# sandwich-logger.net
KiCad netlist of a schematic drawn in EAGLE
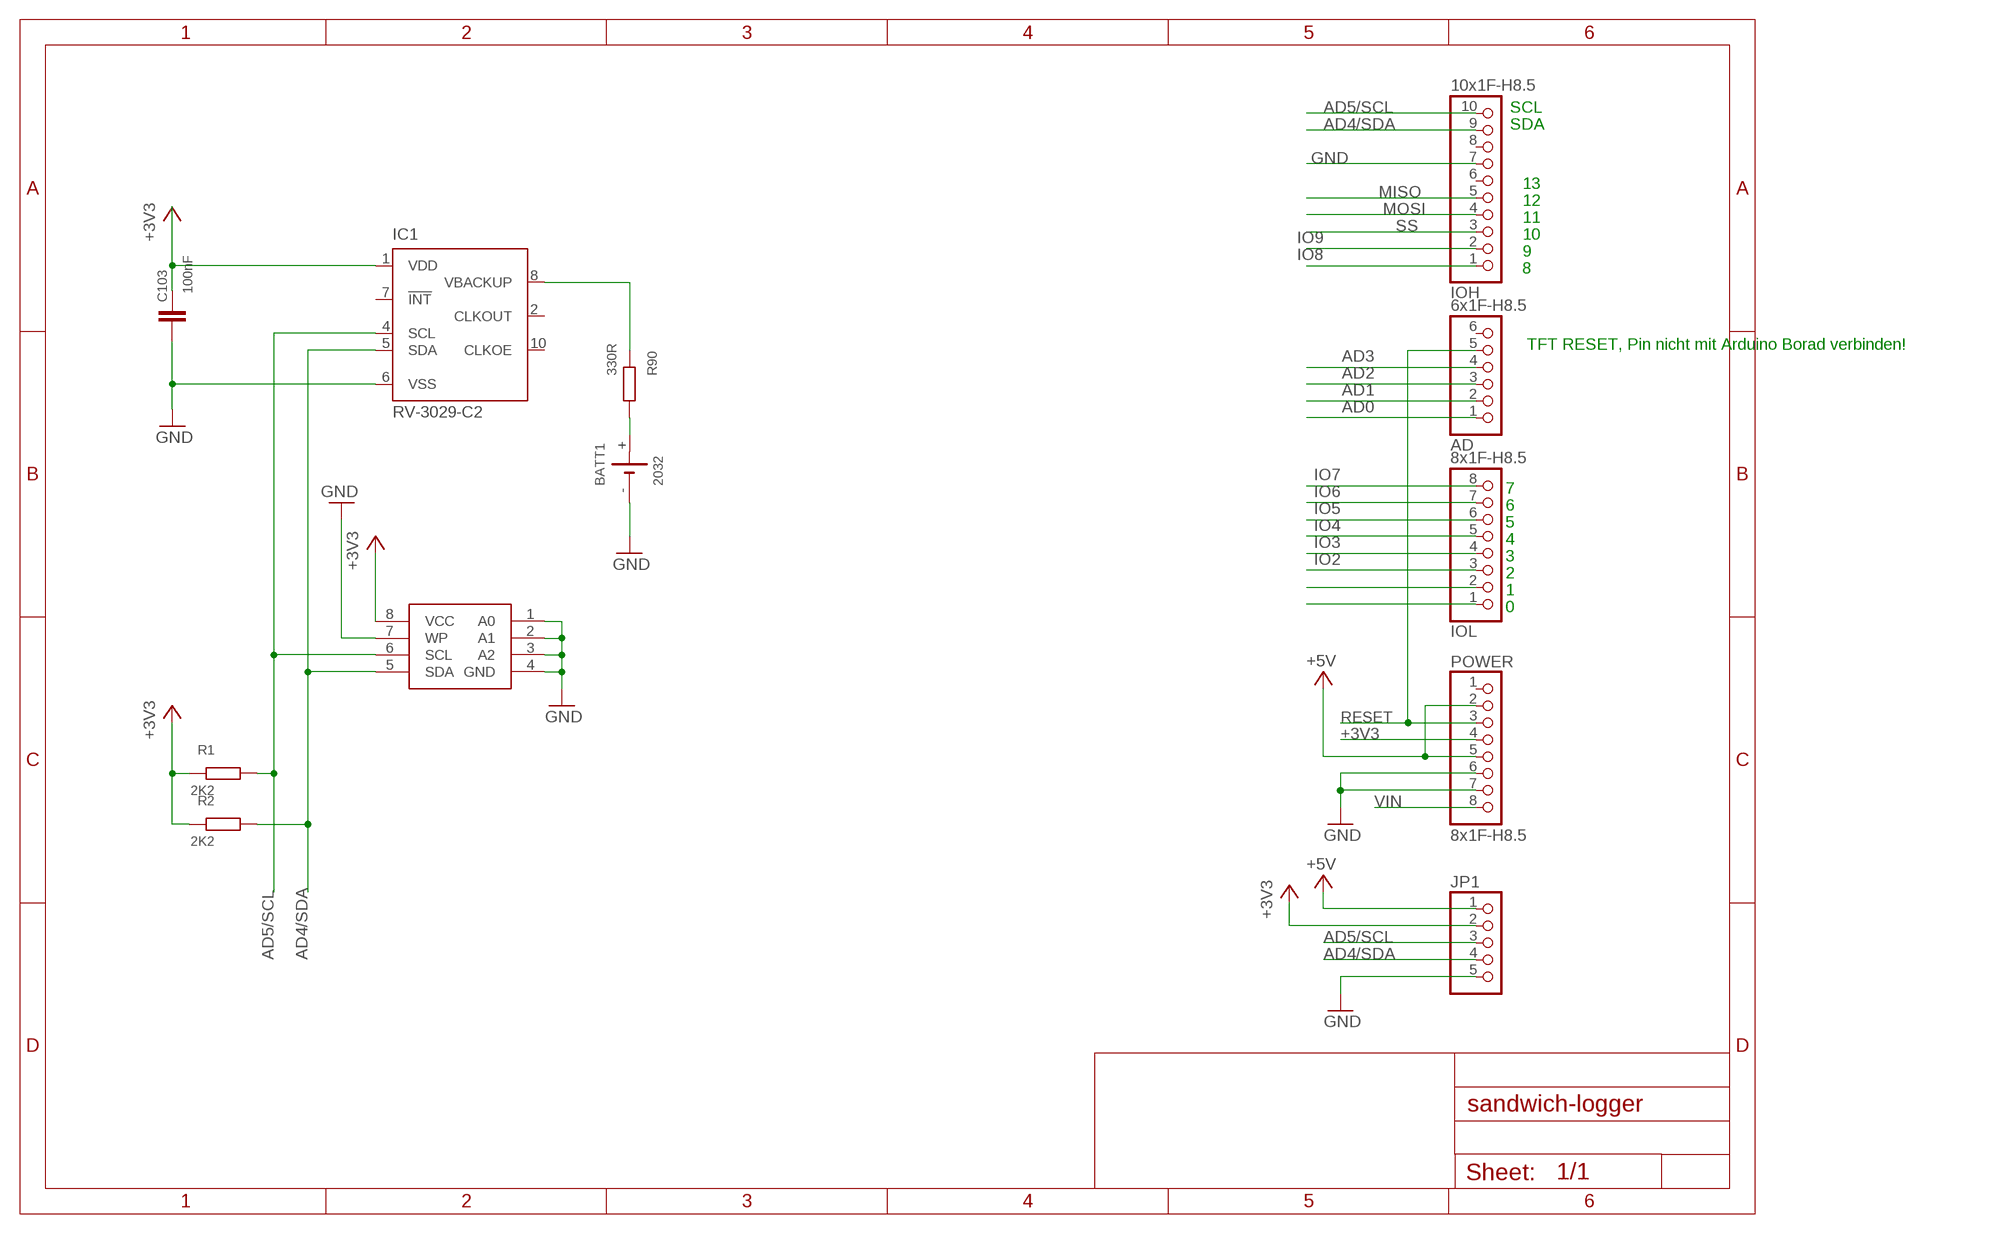
[diagram p0: schematic, sheet 1]

(export (version "E")
  (design (tool "Eeschema 10.0.6"))
  (components
    (comp (ref "AD")
      (value "6x1F-H8.5")
      (footprint "eagle-import:1X06")
      (libsource (lib "eagle-import") (part "PINHD-1X6"))
    )
    (comp (ref "BATT1")
      (value "2032")
      (footprint "eagle-import:2032_SMD")
      (libsource (lib "eagle-import") (part "CR2032_HOLDSMD"))
    )
    (comp (ref "C103")
      (value "100nF")
      (footprint "eagle-import:C0603")
      (libsource (lib "eagle-import") (part "C-EUC0603"))
    )
    (comp (ref "IC1")
      (value "RV-3029-C2")
      (footprint "eagle-import:SON-10")
      (libsource (lib "eagle-import") (part "RV-3029-C2"))
    )
    (comp (ref "IC3")
      (value "AT24C32")
      (footprint "eagle-import:SOIC08")
      (libsource (lib "eagle-import") (part "24C32"))
    )
    (comp (ref "IOH")
      (value "10x1F-H8.5")
      (footprint "eagle-import:1X10")
      (libsource (lib "eagle-import") (part "PINHD-1X10_ARD"))
    )
    (comp (ref "IOL")
      (value "8x1F-H8.5")
      (footprint "eagle-import:1X08")
      (libsource (lib "eagle-import") (part "PINHD-1X8"))
    )
    (comp (ref "JP1")
      (value "PINHD-1X5/90")
      (footprint "eagle-import:1X05_90")
      (libsource (lib "eagle-import") (part "PINHD-1X5/90"))
    )
    (comp (ref "POWER")
      (value "8x1F-H8.5")
      (footprint "eagle-import:1X08")
      (libsource (lib "eagle-import") (part "PINHD-1X8"))
    )
    (comp (ref "R1")
      (value "2K2")
      (footprint "eagle-import:R0603")
      (libsource (lib "eagle-import") (part "R-EU_R0603"))
    )
    (comp (ref "R2")
      (value "2K2")
      (footprint "eagle-import:R0603")
      (libsource (lib "eagle-import") (part "R-EU_R0603"))
    )
    (comp (ref "R90")
      (value "330R")
      (footprint "eagle-import:R0603")
      (libsource (lib "eagle-import") (part "R-EU_R0603"))
    )
  )
  (nets
    (net (code "1") (name "+3V3") (class "Default")
      (node (ref "C103") (pin "1") (pinfunction "1_1") (pintype "passive"))
      (node (ref "IC1") (pin "1") (pinfunction "VDD_1") (pintype "power_in"))
      (node (ref "IC3") (pin "8") (pinfunction "VCC_8") (pintype "bidirectional"))
      (node (ref "JP1") (pin "2") (pinfunction "2_2") (pintype "passive"))
      (node (ref "POWER") (pin "4") (pinfunction "4_4") (pintype "passive"))
      (node (ref "R1") (pin "2") (pinfunction "2_2") (pintype "passive"))
      (node (ref "R2") (pin "2") (pinfunction "2_2") (pintype "passive"))
    )
    (net (code "2") (name "+5V") (class "Default")
      (node (ref "JP1") (pin "1") (pinfunction "1_1") (pintype "passive"))
      (node (ref "POWER") (pin "2") (pinfunction "2_2") (pintype "passive"))
      (node (ref "POWER") (pin "5") (pinfunction "5_5") (pintype "passive"))
    )
    (net (code "3") (name "/AD0") (class "Default")
      (node (ref "AD") (pin "1") (pinfunction "1_1") (pintype "passive"))
    )
    (net (code "4") (name "/AD1") (class "Default")
      (node (ref "AD") (pin "2") (pinfunction "2_2") (pintype "passive"))
    )
    (net (code "5") (name "/AD2") (class "Default")
      (node (ref "AD") (pin "3") (pinfunction "3_3") (pintype "passive"))
    )
    (net (code "6") (name "/AD3") (class "Default")
      (node (ref "AD") (pin "4") (pinfunction "4_4") (pintype "passive"))
    )
    (net (code "7") (name "/AD4{slash}SDA") (class "Default")
      (node (ref "IC1") (pin "5") (pinfunction "SDA_5") (pintype "bidirectional"))
      (node (ref "IC3") (pin "5") (pinfunction "SDA_5") (pintype "bidirectional"))
      (node (ref "IOH") (pin "9") (pinfunction "9_9") (pintype "passive"))
      (node (ref "JP1") (pin "4") (pinfunction "4_4") (pintype "passive"))
      (node (ref "R2") (pin "1") (pinfunction "1_1") (pintype "passive"))
    )
    (net (code "8") (name "/AD5{slash}SCL") (class "Default")
      (node (ref "IC1") (pin "4") (pinfunction "SCL_4") (pintype "input"))
      (node (ref "IC3") (pin "6") (pinfunction "SCL_6") (pintype "bidirectional"))
      (node (ref "IOH") (pin "10") (pinfunction "10_10") (pintype "passive"))
      (node (ref "JP1") (pin "3") (pinfunction "3_3") (pintype "passive"))
      (node (ref "R1") (pin "1") (pinfunction "1_1") (pintype "passive"))
    )
    (net (code "9") (name "/IO2") (class "Default")
      (node (ref "IOL") (pin "3") (pinfunction "3_3") (pintype "passive"))
    )
    (net (code "10") (name "/IO3") (class "Default")
      (node (ref "IOL") (pin "4") (pinfunction "4_4") (pintype "passive"))
    )
    (net (code "11") (name "/IO4") (class "Default")
      (node (ref "IOL") (pin "5") (pinfunction "5_5") (pintype "passive"))
    )
    (net (code "12") (name "/IO5") (class "Default")
      (node (ref "IOL") (pin "6") (pinfunction "6_6") (pintype "passive"))
    )
    (net (code "13") (name "/IO6") (class "Default")
      (node (ref "IOL") (pin "7") (pinfunction "7_7") (pintype "passive"))
    )
    (net (code "14") (name "/IO7") (class "Default")
      (node (ref "IOL") (pin "8") (pinfunction "8_8") (pintype "passive"))
    )
    (net (code "15") (name "/IO8") (class "Default")
      (node (ref "IOH") (pin "1") (pinfunction "1_1") (pintype "passive"))
    )
    (net (code "16") (name "/IO9") (class "Default")
      (node (ref "IOH") (pin "2") (pinfunction "2_2") (pintype "passive"))
    )
    (net (code "17") (name "/MISO") (class "Default")
      (node (ref "IOH") (pin "5") (pinfunction "5_5") (pintype "passive"))
    )
    (net (code "18") (name "/MOSI") (class "Default")
      (node (ref "IOH") (pin "4") (pinfunction "4_4") (pintype "passive"))
    )
    (net (code "19") (name "/RESET") (class "Default")
      (node (ref "AD") (pin "5") (pinfunction "5_5") (pintype "passive"))
      (node (ref "POWER") (pin "3") (pinfunction "3_3") (pintype "passive"))
    )
    (net (code "20") (name "/SS") (class "Default")
      (node (ref "IOH") (pin "3") (pinfunction "3_3") (pintype "passive"))
    )
    (net (code "21") (name "/VIN") (class "Default")
      (node (ref "POWER") (pin "8") (pinfunction "8_8") (pintype "passive"))
    )
    (net (code "22") (name "GND") (class "Default")
      (node (ref "BATT1") (pin "-") (pinfunction "-_-") (pintype "passive"))
      (node (ref "C103") (pin "2") (pinfunction "2_2") (pintype "passive"))
      (node (ref "IC1") (pin "6") (pinfunction "VSS_6") (pintype "power_in"))
      (node (ref "IC3") (pin "1") (pinfunction "A0_1") (pintype "bidirectional"))
      (node (ref "IC3") (pin "2") (pinfunction "A1_2") (pintype "bidirectional"))
      (node (ref "IC3") (pin "3") (pinfunction "A2_3") (pintype "bidirectional"))
      (node (ref "IC3") (pin "4") (pinfunction "GND_4") (pintype "bidirectional"))
      (node (ref "IC3") (pin "7") (pinfunction "WP_7") (pintype "bidirectional"))
      (node (ref "IOH") (pin "7") (pinfunction "7_7") (pintype "passive"))
      (node (ref "JP1") (pin "5") (pinfunction "5_5") (pintype "passive"))
      (node (ref "POWER") (pin "6") (pinfunction "6_6") (pintype "passive"))
      (node (ref "POWER") (pin "7") (pinfunction "7_7") (pintype "passive"))
    )
    (net (code "23") (name "Net-(BATT1-Pad+)") (class "Default")
      (node (ref "BATT1") (pin "+") (pinfunction "+_+") (pintype "passive"))
      (node (ref "R90") (pin "1") (pinfunction "1_1") (pintype "passive"))
    )
    (net (code "24") (name "Net-(IC1-VBACKUP)") (class "Default")
      (node (ref "IC1") (pin "8") (pinfunction "VBACKUP_8") (pintype "input"))
      (node (ref "R90") (pin "2") (pinfunction "2_2") (pintype "passive"))
    )
    (net (code "25") (name "unconnected-(AD-Pad6)") (class "Default")
      (node (ref "AD") (pin "6") (pinfunction "6_6") (pintype "passive"))
    )
    (net (code "26") (name "unconnected-(IC1-CLKOE-Pad10)") (class "Default")
      (node (ref "IC1") (pin "10") (pinfunction "CLKOE_10") (pintype "input"))
    )
    (net (code "27") (name "unconnected-(IC1-CLKOUT-Pad2)") (class "Default")
      (node (ref "IC1") (pin "2") (pinfunction "CLKOUT_2") (pintype "output"))
    )
    (net (code "28") (name "unconnected-(IC1-~{INT}-Pad7)") (class "Default")
      (node (ref "IC1") (pin "7") (pinfunction "~{INT}_7") (pintype "input"))
    )
    (net (code "29") (name "unconnected-(IOH-Pad6)") (class "Default")
      (node (ref "IOH") (pin "6") (pinfunction "6_6") (pintype "passive"))
    )
    (net (code "30") (name "unconnected-(IOH-Pad8)") (class "Default")
      (node (ref "IOH") (pin "8") (pinfunction "8_8") (pintype "passive"))
    )
    (net (code "31") (name "unconnected-(IOL-Pad1)") (class "Default")
      (node (ref "IOL") (pin "1") (pinfunction "1_1") (pintype "passive"))
    )
    (net (code "32") (name "unconnected-(IOL-Pad2)") (class "Default")
      (node (ref "IOL") (pin "2") (pinfunction "2_2") (pintype "passive"))
    )
    (net (code "33") (name "unconnected-(POWER-Pad1)") (class "Default")
      (node (ref "POWER") (pin "1") (pinfunction "1_1") (pintype "passive"))
    )
  )
)
